# V_Sns_I2C_Isolators.net
KiCad netlist of a schematic drawn in Altium Designer
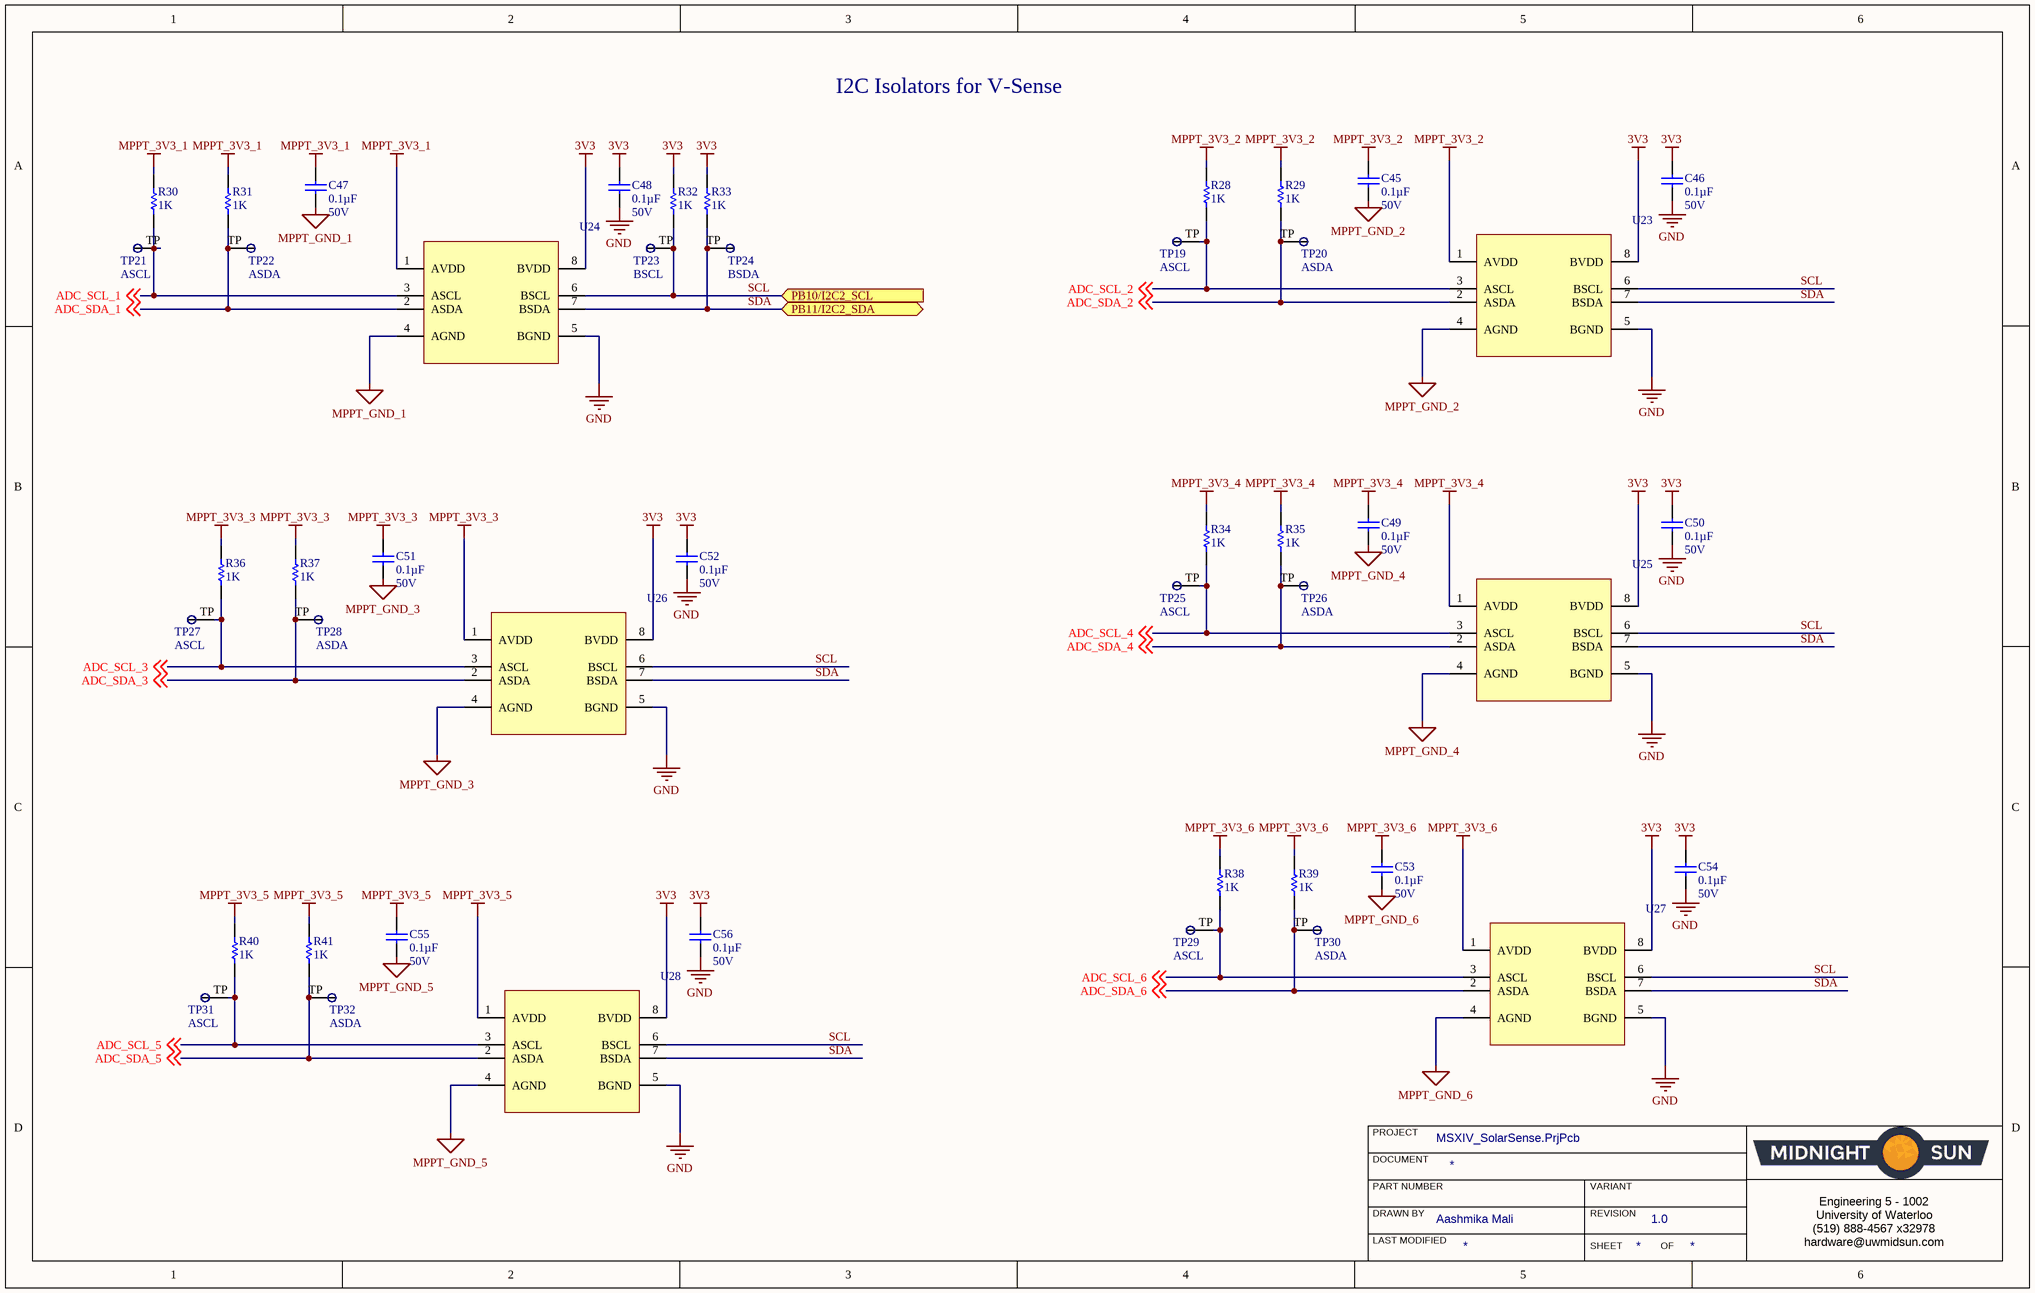
[diagram p0: V_Sns_I2C_Isolators.SchDoc]

(export (version "E")
  (design (tool "Eeschema 10.0.6"))
  (components
    (comp (ref "C45")
      (value "CAP CER 0.1UF 50V 10% X7R 0603")
      (footprint "CAP, 0603")
      (description "0.10µF ±10% 50V Ceramic Capacitor X7R 0603 (1608 Metric)")
      (fields
        (field (name "TOLERANCE") "±10%")
        (field (name "CAPACITANCE") "0.1µF")
        (field (name "VOLTAGE") "50V")
      )
      (libsource (lib "Schematic Diagrams") (part "CAP CER 0.1UF 50V 10% X7R 0603"))
    )
    (comp (ref "C46")
      (value "CAP CER 0.1UF 50V 10% X7R 0603")
      (footprint "CAP, 0603")
      (description "0.10µF ±10% 50V Ceramic Capacitor X7R 0603 (1608 Metric)")
      (fields
        (field (name "TOLERANCE") "±10%")
        (field (name "CAPACITANCE") "0.1µF")
        (field (name "VOLTAGE") "50V")
      )
      (libsource (lib "Schematic Diagrams") (part "CAP CER 0.1UF 50V 10% X7R 0603"))
    )
    (comp (ref "C47")
      (value "CAP CER 0.1UF 50V 10% X7R 0603")
      (footprint "CAP, 0603")
      (description "0.10µF ±10% 50V Ceramic Capacitor X7R 0603 (1608 Metric)")
      (fields
        (field (name "TOLERANCE") "±10%")
        (field (name "CAPACITANCE") "0.1µF")
        (field (name "VOLTAGE") "50V")
      )
      (libsource (lib "Schematic Diagrams") (part "CAP CER 0.1UF 50V 10% X7R 0603"))
    )
    (comp (ref "C48")
      (value "CAP CER 0.1UF 50V 10% X7R 0603")
      (footprint "CAP, 0603")
      (description "0.10µF ±10% 50V Ceramic Capacitor X7R 0603 (1608 Metric)")
      (fields
        (field (name "TOLERANCE") "±10%")
        (field (name "CAPACITANCE") "0.1µF")
        (field (name "VOLTAGE") "50V")
      )
      (libsource (lib "Schematic Diagrams") (part "CAP CER 0.1UF 50V 10% X7R 0603"))
    )
    (comp (ref "C49")
      (value "CAP CER 0.1UF 50V 10% X7R 0603")
      (footprint "CAP, 0603")
      (description "0.10µF ±10% 50V Ceramic Capacitor X7R 0603 (1608 Metric)")
      (fields
        (field (name "TOLERANCE") "±10%")
        (field (name "CAPACITANCE") "0.1µF")
        (field (name "VOLTAGE") "50V")
      )
      (libsource (lib "Schematic Diagrams") (part "CAP CER 0.1UF 50V 10% X7R 0603"))
    )
    (comp (ref "C50")
      (value "CAP CER 0.1UF 50V 10% X7R 0603")
      (footprint "CAP, 0603")
      (description "0.10µF ±10% 50V Ceramic Capacitor X7R 0603 (1608 Metric)")
      (fields
        (field (name "TOLERANCE") "±10%")
        (field (name "CAPACITANCE") "0.1µF")
        (field (name "VOLTAGE") "50V")
      )
      (libsource (lib "Schematic Diagrams") (part "CAP CER 0.1UF 50V 10% X7R 0603"))
    )
    (comp (ref "C51")
      (value "CAP CER 0.1UF 50V 10% X7R 0603")
      (footprint "CAP, 0603")
      (description "0.10µF ±10% 50V Ceramic Capacitor X7R 0603 (1608 Metric)")
      (fields
        (field (name "TOLERANCE") "±10%")
        (field (name "CAPACITANCE") "0.1µF")
        (field (name "VOLTAGE") "50V")
      )
      (libsource (lib "Schematic Diagrams") (part "CAP CER 0.1UF 50V 10% X7R 0603"))
    )
    (comp (ref "C52")
      (value "CAP CER 0.1UF 50V 10% X7R 0603")
      (footprint "CAP, 0603")
      (description "0.10µF ±10% 50V Ceramic Capacitor X7R 0603 (1608 Metric)")
      (fields
        (field (name "TOLERANCE") "±10%")
        (field (name "CAPACITANCE") "0.1µF")
        (field (name "VOLTAGE") "50V")
      )
      (libsource (lib "Schematic Diagrams") (part "CAP CER 0.1UF 50V 10% X7R 0603"))
    )
    (comp (ref "C53")
      (value "CAP CER 0.1UF 50V 10% X7R 0603")
      (footprint "CAP, 0603")
      (description "0.10µF ±10% 50V Ceramic Capacitor X7R 0603 (1608 Metric)")
      (fields
        (field (name "TOLERANCE") "±10%")
        (field (name "CAPACITANCE") "0.1µF")
        (field (name "VOLTAGE") "50V")
      )
      (libsource (lib "Schematic Diagrams") (part "CAP CER 0.1UF 50V 10% X7R 0603"))
    )
    (comp (ref "C54")
      (value "CAP CER 0.1UF 50V 10% X7R 0603")
      (footprint "CAP, 0603")
      (description "0.10µF ±10% 50V Ceramic Capacitor X7R 0603 (1608 Metric)")
      (fields
        (field (name "TOLERANCE") "±10%")
        (field (name "CAPACITANCE") "0.1µF")
        (field (name "VOLTAGE") "50V")
      )
      (libsource (lib "Schematic Diagrams") (part "CAP CER 0.1UF 50V 10% X7R 0603"))
    )
    (comp (ref "C55")
      (value "CAP CER 0.1UF 50V 10% X7R 0603")
      (footprint "CAP, 0603")
      (description "0.10µF ±10% 50V Ceramic Capacitor X7R 0603 (1608 Metric)")
      (fields
        (field (name "TOLERANCE") "±10%")
        (field (name "CAPACITANCE") "0.1µF")
        (field (name "VOLTAGE") "50V")
      )
      (libsource (lib "Schematic Diagrams") (part "CAP CER 0.1UF 50V 10% X7R 0603"))
    )
    (comp (ref "C56")
      (value "CAP CER 0.1UF 50V 10% X7R 0603")
      (footprint "CAP, 0603")
      (description "0.10µF ±10% 50V Ceramic Capacitor X7R 0603 (1608 Metric)")
      (fields
        (field (name "TOLERANCE") "±10%")
        (field (name "CAPACITANCE") "0.1µF")
        (field (name "VOLTAGE") "50V")
      )
      (libsource (lib "Schematic Diagrams") (part "CAP CER 0.1UF 50V 10% X7R 0603"))
    )
    (comp (ref "R28")
      (value "1K")
      (footprint "RES, 0603")
      (description "1k Ohm ±5% 0.1W, 1/10W Chip Resistor 0603 (1608 Metric)")
      (fields
        (field (name "MANUFACTURER") "Yageo")
        (field (name "MANUFACTURER PART NUMBER") "RC0603JR-071KL")
      )
      (libsource (lib "Schematic Diagrams") (part "RES 1K OHM 5% 1/10W 0603"))
    )
    (comp (ref "R29")
      (value "1K")
      (footprint "RES, 0603")
      (description "1k Ohm ±5% 0.1W, 1/10W Chip Resistor 0603 (1608 Metric)")
      (fields
        (field (name "MANUFACTURER") "Yageo")
        (field (name "MANUFACTURER PART NUMBER") "RC0603JR-071KL")
      )
      (libsource (lib "Schematic Diagrams") (part "RES 1K OHM 5% 1/10W 0603"))
    )
    (comp (ref "R30")
      (value "1K")
      (footprint "RES, 0603")
      (description "1k Ohm ±5% 0.1W, 1/10W Chip Resistor 0603 (1608 Metric)")
      (fields
        (field (name "MANUFACTURER") "Yageo")
        (field (name "MANUFACTURER PART NUMBER") "RC0603JR-071KL")
      )
      (libsource (lib "Schematic Diagrams") (part "RES 1K OHM 5% 1/10W 0603"))
    )
    (comp (ref "R31")
      (value "1K")
      (footprint "RES, 0603")
      (description "1k Ohm ±5% 0.1W, 1/10W Chip Resistor 0603 (1608 Metric)")
      (fields
        (field (name "MANUFACTURER") "Yageo")
        (field (name "MANUFACTURER PART NUMBER") "RC0603JR-071KL")
      )
      (libsource (lib "Schematic Diagrams") (part "RES 1K OHM 5% 1/10W 0603"))
    )
    (comp (ref "R32")
      (value "1K")
      (footprint "RES, 0603")
      (description "1k Ohm ±5% 0.1W, 1/10W Chip Resistor 0603 (1608 Metric)")
      (fields
        (field (name "MANUFACTURER") "Yageo")
        (field (name "MANUFACTURER PART NUMBER") "RC0603JR-071KL")
      )
      (libsource (lib "Schematic Diagrams") (part "RES 1K OHM 5% 1/10W 0603"))
    )
    (comp (ref "R33")
      (value "1K")
      (footprint "RES, 0603")
      (description "1k Ohm ±5% 0.1W, 1/10W Chip Resistor 0603 (1608 Metric)")
      (fields
        (field (name "MANUFACTURER") "Yageo")
        (field (name "MANUFACTURER PART NUMBER") "RC0603JR-071KL")
      )
      (libsource (lib "Schematic Diagrams") (part "RES 1K OHM 5% 1/10W 0603"))
    )
    (comp (ref "R34")
      (value "1K")
      (footprint "RES, 0603")
      (description "1k Ohm ±5% 0.1W, 1/10W Chip Resistor 0603 (1608 Metric)")
      (fields
        (field (name "MANUFACTURER") "Yageo")
        (field (name "MANUFACTURER PART NUMBER") "RC0603JR-071KL")
      )
      (libsource (lib "Schematic Diagrams") (part "RES 1K OHM 5% 1/10W 0603"))
    )
    (comp (ref "R35")
      (value "1K")
      (footprint "RES, 0603")
      (description "1k Ohm ±5% 0.1W, 1/10W Chip Resistor 0603 (1608 Metric)")
      (fields
        (field (name "MANUFACTURER") "Yageo")
        (field (name "MANUFACTURER PART NUMBER") "RC0603JR-071KL")
      )
      (libsource (lib "Schematic Diagrams") (part "RES 1K OHM 5% 1/10W 0603"))
    )
    (comp (ref "R36")
      (value "1K")
      (footprint "RES, 0603")
      (description "1k Ohm ±5% 0.1W, 1/10W Chip Resistor 0603 (1608 Metric)")
      (fields
        (field (name "MANUFACTURER") "Yageo")
        (field (name "MANUFACTURER PART NUMBER") "RC0603JR-071KL")
      )
      (libsource (lib "Schematic Diagrams") (part "RES 1K OHM 5% 1/10W 0603"))
    )
    (comp (ref "R37")
      (value "1K")
      (footprint "RES, 0603")
      (description "1k Ohm ±5% 0.1W, 1/10W Chip Resistor 0603 (1608 Metric)")
      (fields
        (field (name "MANUFACTURER") "Yageo")
        (field (name "MANUFACTURER PART NUMBER") "RC0603JR-071KL")
      )
      (libsource (lib "Schematic Diagrams") (part "RES 1K OHM 5% 1/10W 0603"))
    )
    (comp (ref "R38")
      (value "1K")
      (footprint "RES, 0603")
      (description "1k Ohm ±5% 0.1W, 1/10W Chip Resistor 0603 (1608 Metric)")
      (fields
        (field (name "MANUFACTURER") "Yageo")
        (field (name "MANUFACTURER PART NUMBER") "RC0603JR-071KL")
      )
      (libsource (lib "Schematic Diagrams") (part "RES 1K OHM 5% 1/10W 0603"))
    )
    (comp (ref "R39")
      (value "1K")
      (footprint "RES, 0603")
      (description "1k Ohm ±5% 0.1W, 1/10W Chip Resistor 0603 (1608 Metric)")
      (fields
        (field (name "MANUFACTURER") "Yageo")
        (field (name "MANUFACTURER PART NUMBER") "RC0603JR-071KL")
      )
      (libsource (lib "Schematic Diagrams") (part "RES 1K OHM 5% 1/10W 0603"))
    )
    (comp (ref "R40")
      (value "1K")
      (footprint "RES, 0603")
      (description "1k Ohm ±5% 0.1W, 1/10W Chip Resistor 0603 (1608 Metric)")
      (fields
        (field (name "MANUFACTURER") "Yageo")
        (field (name "MANUFACTURER PART NUMBER") "RC0603JR-071KL")
      )
      (libsource (lib "Schematic Diagrams") (part "RES 1K OHM 5% 1/10W 0603"))
    )
    (comp (ref "R41")
      (value "1K")
      (footprint "RES, 0603")
      (description "1k Ohm ±5% 0.1W, 1/10W Chip Resistor 0603 (1608 Metric)")
      (fields
        (field (name "MANUFACTURER") "Yageo")
        (field (name "MANUFACTURER PART NUMBER") "RC0603JR-071KL")
      )
      (libsource (lib "Schematic Diagrams") (part "RES 1K OHM 5% 1/10W 0603"))
    )
    (comp (ref "TP19")
      (value "ASCL")
      (footprint "Test Point")
      (libsource (lib "Schematic Diagrams") (part "Test Point"))
    )
    (comp (ref "TP20")
      (value "ASDA")
      (footprint "Test Point")
      (libsource (lib "Schematic Diagrams") (part "Test Point"))
    )
    (comp (ref "TP21")
      (value "ASCL")
      (footprint "Test Point")
      (libsource (lib "Schematic Diagrams") (part "Test Point"))
    )
    (comp (ref "TP22")
      (value "ASDA")
      (footprint "Test Point")
      (libsource (lib "Schematic Diagrams") (part "Test Point"))
    )
    (comp (ref "TP23")
      (value "BSCL")
      (footprint "Test Point")
      (libsource (lib "Schematic Diagrams") (part "Test Point"))
    )
    (comp (ref "TP24")
      (value "BSDA")
      (footprint "Test Point")
      (libsource (lib "Schematic Diagrams") (part "Test Point"))
    )
    (comp (ref "TP25")
      (value "ASCL")
      (footprint "Test Point")
      (libsource (lib "Schematic Diagrams") (part "Test Point"))
    )
    (comp (ref "TP26")
      (value "ASDA")
      (footprint "Test Point")
      (libsource (lib "Schematic Diagrams") (part "Test Point"))
    )
    (comp (ref "TP27")
      (value "ASCL")
      (footprint "Test Point")
      (libsource (lib "Schematic Diagrams") (part "Test Point"))
    )
    (comp (ref "TP28")
      (value "ASDA")
      (footprint "Test Point")
      (libsource (lib "Schematic Diagrams") (part "Test Point"))
    )
    (comp (ref "TP29")
      (value "ASCL")
      (footprint "Test Point")
      (libsource (lib "Schematic Diagrams") (part "Test Point"))
    )
    (comp (ref "TP30")
      (value "ASDA")
      (footprint "Test Point")
      (libsource (lib "Schematic Diagrams") (part "Test Point"))
    )
    (comp (ref "TP31")
      (value "ASCL")
      (footprint "Test Point")
      (libsource (lib "Schematic Diagrams") (part "Test Point"))
    )
    (comp (ref "TP32")
      (value "ASDA")
      (footprint "Test Point")
      (libsource (lib "Schematic Diagrams") (part "Test Point"))
    )
    (comp (ref "U23")
      (value "IC DGTL ISO 2.5KV 2CH I2C 8SOIC ISO1540DR")
      (footprint "SOIC-8 ISO1540DR")
      (description "I²C Digital Isolator 2500Vrms 2 Channel 1Mbps 25kV/µs CMTI 8-SOIC (0.154\", 3.90mm Width)")
      (fields
        (field (name "MANUFACTURER") "Texas Instruments")
        (field (name "MANUFACTURER PART NUMBER") "ISO1540DR")
      )
      (libsource (lib "Schematic Diagrams") (part "IC DGTL ISO 2.5KV 2CH I2C 8SOIC ISO1540DR"))
    )
    (comp (ref "U24")
      (value "IC DGTL ISO 2.5KV 2CH I2C 8SOIC ISO1540DR")
      (footprint "SOIC-8 ISO1540DR")
      (description "I²C Digital Isolator 2500Vrms 2 Channel 1Mbps 25kV/µs CMTI 8-SOIC (0.154\", 3.90mm Width)")
      (fields
        (field (name "MANUFACTURER") "Texas Instruments")
        (field (name "MANUFACTURER PART NUMBER") "ISO1540DR")
      )
      (libsource (lib "Schematic Diagrams") (part "IC DGTL ISO 2.5KV 2CH I2C 8SOIC ISO1540DR"))
    )
    (comp (ref "U25")
      (value "IC DGTL ISO 2.5KV 2CH I2C 8SOIC ISO1540DR")
      (footprint "SOIC-8 ISO1540DR")
      (description "I²C Digital Isolator 2500Vrms 2 Channel 1Mbps 25kV/µs CMTI 8-SOIC (0.154\", 3.90mm Width)")
      (fields
        (field (name "MANUFACTURER") "Texas Instruments")
        (field (name "MANUFACTURER PART NUMBER") "ISO1540DR")
      )
      (libsource (lib "Schematic Diagrams") (part "IC DGTL ISO 2.5KV 2CH I2C 8SOIC ISO1540DR"))
    )
    (comp (ref "U26")
      (value "IC DGTL ISO 2.5KV 2CH I2C 8SOIC ISO1540DR")
      (footprint "SOIC-8 ISO1540DR")
      (description "I²C Digital Isolator 2500Vrms 2 Channel 1Mbps 25kV/µs CMTI 8-SOIC (0.154\", 3.90mm Width)")
      (fields
        (field (name "MANUFACTURER") "Texas Instruments")
        (field (name "MANUFACTURER PART NUMBER") "ISO1540DR")
      )
      (libsource (lib "Schematic Diagrams") (part "IC DGTL ISO 2.5KV 2CH I2C 8SOIC ISO1540DR"))
    )
    (comp (ref "U27")
      (value "IC DGTL ISO 2.5KV 2CH I2C 8SOIC ISO1540DR")
      (footprint "SOIC-8 ISO1540DR")
      (description "I²C Digital Isolator 2500Vrms 2 Channel 1Mbps 25kV/µs CMTI 8-SOIC (0.154\", 3.90mm Width)")
      (fields
        (field (name "MANUFACTURER") "Texas Instruments")
        (field (name "MANUFACTURER PART NUMBER") "ISO1540DR")
      )
      (libsource (lib "Schematic Diagrams") (part "IC DGTL ISO 2.5KV 2CH I2C 8SOIC ISO1540DR"))
    )
    (comp (ref "U28")
      (value "IC DGTL ISO 2.5KV 2CH I2C 8SOIC ISO1540DR")
      (footprint "SOIC-8 ISO1540DR")
      (description "I²C Digital Isolator 2500Vrms 2 Channel 1Mbps 25kV/µs CMTI 8-SOIC (0.154\", 3.90mm Width)")
      (fields
        (field (name "MANUFACTURER") "Texas Instruments")
        (field (name "MANUFACTURER PART NUMBER") "ISO1540DR")
      )
      (libsource (lib "Schematic Diagrams") (part "IC DGTL ISO 2.5KV 2CH I2C 8SOIC ISO1540DR"))
    )
  )
  (nets
    (net (code "1") (name "/SCL") (class "Default")
      (node (ref "R32") (pin "2") (pinfunction "2_2") (pintype "passive"))
      (node (ref "TP23") (pin "TP") (pinfunction "1_TP") (pintype "passive"))
      (node (ref "U23") (pin "6") (pinfunction "BSCL_6") (pintype "passive"))
      (node (ref "U24") (pin "6") (pinfunction "BSCL_6") (pintype "passive"))
      (node (ref "U25") (pin "6") (pinfunction "BSCL_6") (pintype "passive"))
      (node (ref "U26") (pin "6") (pinfunction "BSCL_6") (pintype "passive"))
      (node (ref "U27") (pin "6") (pinfunction "BSCL_6") (pintype "passive"))
      (node (ref "U28") (pin "6") (pinfunction "BSCL_6") (pintype "passive"))
    )
    (net (code "2") (name "/SDA") (class "Default")
      (node (ref "R33") (pin "2") (pinfunction "2_2") (pintype "passive"))
      (node (ref "TP24") (pin "TP") (pinfunction "1_TP") (pintype "passive"))
      (node (ref "U23") (pin "7") (pinfunction "BSDA_7") (pintype "passive"))
      (node (ref "U24") (pin "7") (pinfunction "BSDA_7") (pintype "passive"))
      (node (ref "U25") (pin "7") (pinfunction "BSDA_7") (pintype "passive"))
      (node (ref "U26") (pin "7") (pinfunction "BSDA_7") (pintype "passive"))
      (node (ref "U27") (pin "7") (pinfunction "BSDA_7") (pintype "passive"))
      (node (ref "U28") (pin "7") (pinfunction "BSDA_7") (pintype "passive"))
    )
    (net (code "3") (name "3V3") (class "Default")
      (node (ref "C46") (pin "1") (pinfunction "1_1") (pintype "passive"))
      (node (ref "C48") (pin "1") (pinfunction "1_1") (pintype "passive"))
      (node (ref "C50") (pin "1") (pinfunction "1_1") (pintype "passive"))
      (node (ref "C52") (pin "1") (pinfunction "1_1") (pintype "passive"))
      (node (ref "C54") (pin "1") (pinfunction "1_1") (pintype "passive"))
      (node (ref "C56") (pin "1") (pinfunction "1_1") (pintype "passive"))
      (node (ref "R32") (pin "1") (pinfunction "1_1") (pintype "passive"))
      (node (ref "R33") (pin "1") (pinfunction "1_1") (pintype "passive"))
      (node (ref "U23") (pin "8") (pinfunction "BVDD_8") (pintype "passive"))
      (node (ref "U24") (pin "8") (pinfunction "BVDD_8") (pintype "passive"))
      (node (ref "U25") (pin "8") (pinfunction "BVDD_8") (pintype "passive"))
      (node (ref "U26") (pin "8") (pinfunction "BVDD_8") (pintype "passive"))
      (node (ref "U27") (pin "8") (pinfunction "BVDD_8") (pintype "passive"))
      (node (ref "U28") (pin "8") (pinfunction "BVDD_8") (pintype "passive"))
    )
    (net (code "4") (name "ADC_SCL_1") (class "Default")
      (node (ref "R30") (pin "2") (pinfunction "2_2") (pintype "passive"))
      (node (ref "TP21") (pin "TP") (pinfunction "1_TP") (pintype "passive"))
      (node (ref "U24") (pin "3") (pinfunction "ASCL_3") (pintype "open_collector"))
    )
    (net (code "5") (name "ADC_SCL_2") (class "Default")
      (node (ref "R28") (pin "2") (pinfunction "2_2") (pintype "passive"))
      (node (ref "TP19") (pin "TP") (pinfunction "1_TP") (pintype "passive"))
      (node (ref "U23") (pin "3") (pinfunction "ASCL_3") (pintype "open_collector"))
    )
    (net (code "6") (name "ADC_SCL_3") (class "Default")
      (node (ref "R36") (pin "2") (pinfunction "2_2") (pintype "passive"))
      (node (ref "TP27") (pin "TP") (pinfunction "1_TP") (pintype "passive"))
      (node (ref "U26") (pin "3") (pinfunction "ASCL_3") (pintype "open_collector"))
    )
    (net (code "7") (name "ADC_SCL_4") (class "Default")
      (node (ref "R34") (pin "2") (pinfunction "2_2") (pintype "passive"))
      (node (ref "TP25") (pin "TP") (pinfunction "1_TP") (pintype "passive"))
      (node (ref "U25") (pin "3") (pinfunction "ASCL_3") (pintype "open_collector"))
    )
    (net (code "8") (name "ADC_SCL_5") (class "Default")
      (node (ref "R40") (pin "2") (pinfunction "2_2") (pintype "passive"))
      (node (ref "TP31") (pin "TP") (pinfunction "1_TP") (pintype "passive"))
      (node (ref "U28") (pin "3") (pinfunction "ASCL_3") (pintype "open_collector"))
    )
    (net (code "9") (name "ADC_SCL_6") (class "Default")
      (node (ref "R38") (pin "2") (pinfunction "2_2") (pintype "passive"))
      (node (ref "TP29") (pin "TP") (pinfunction "1_TP") (pintype "passive"))
      (node (ref "U27") (pin "3") (pinfunction "ASCL_3") (pintype "open_collector"))
    )
    (net (code "10") (name "ADC_SDA_1") (class "Default")
      (node (ref "R31") (pin "2") (pinfunction "2_2") (pintype "passive"))
      (node (ref "TP22") (pin "TP") (pinfunction "1_TP") (pintype "passive"))
      (node (ref "U24") (pin "2") (pinfunction "ASDA_2") (pintype "open_collector"))
    )
    (net (code "11") (name "ADC_SDA_2") (class "Default")
      (node (ref "R29") (pin "2") (pinfunction "2_2") (pintype "passive"))
      (node (ref "TP20") (pin "TP") (pinfunction "1_TP") (pintype "passive"))
      (node (ref "U23") (pin "2") (pinfunction "ASDA_2") (pintype "open_collector"))
    )
    (net (code "12") (name "ADC_SDA_3") (class "Default")
      (node (ref "R37") (pin "2") (pinfunction "2_2") (pintype "passive"))
      (node (ref "TP28") (pin "TP") (pinfunction "1_TP") (pintype "passive"))
      (node (ref "U26") (pin "2") (pinfunction "ASDA_2") (pintype "open_collector"))
    )
    (net (code "13") (name "ADC_SDA_4") (class "Default")
      (node (ref "R35") (pin "2") (pinfunction "2_2") (pintype "passive"))
      (node (ref "TP26") (pin "TP") (pinfunction "1_TP") (pintype "passive"))
      (node (ref "U25") (pin "2") (pinfunction "ASDA_2") (pintype "open_collector"))
    )
    (net (code "14") (name "ADC_SDA_5") (class "Default")
      (node (ref "R41") (pin "2") (pinfunction "2_2") (pintype "passive"))
      (node (ref "TP32") (pin "TP") (pinfunction "1_TP") (pintype "passive"))
      (node (ref "U28") (pin "2") (pinfunction "ASDA_2") (pintype "open_collector"))
    )
    (net (code "15") (name "ADC_SDA_6") (class "Default")
      (node (ref "R39") (pin "2") (pinfunction "2_2") (pintype "passive"))
      (node (ref "TP30") (pin "TP") (pinfunction "1_TP") (pintype "passive"))
      (node (ref "U27") (pin "2") (pinfunction "ASDA_2") (pintype "open_collector"))
    )
    (net (code "16") (name "GND") (class "Default")
      (node (ref "C46") (pin "2") (pinfunction "2_2") (pintype "passive"))
      (node (ref "C48") (pin "2") (pinfunction "2_2") (pintype "passive"))
      (node (ref "C50") (pin "2") (pinfunction "2_2") (pintype "passive"))
      (node (ref "C52") (pin "2") (pinfunction "2_2") (pintype "passive"))
      (node (ref "C54") (pin "2") (pinfunction "2_2") (pintype "passive"))
      (node (ref "C56") (pin "2") (pinfunction "2_2") (pintype "passive"))
      (node (ref "U23") (pin "5") (pinfunction "BGND_5") (pintype "passive"))
      (node (ref "U24") (pin "5") (pinfunction "BGND_5") (pintype "passive"))
      (node (ref "U25") (pin "5") (pinfunction "BGND_5") (pintype "passive"))
      (node (ref "U26") (pin "5") (pinfunction "BGND_5") (pintype "passive"))
      (node (ref "U27") (pin "5") (pinfunction "BGND_5") (pintype "passive"))
      (node (ref "U28") (pin "5") (pinfunction "BGND_5") (pintype "passive"))
    )
    (net (code "17") (name "MPPT_3V3_1") (class "Default")
      (node (ref "C47") (pin "1") (pinfunction "1_1") (pintype "passive"))
      (node (ref "R30") (pin "1") (pinfunction "1_1") (pintype "passive"))
      (node (ref "R31") (pin "1") (pinfunction "1_1") (pintype "passive"))
      (node (ref "U24") (pin "1") (pinfunction "AVDD_1") (pintype "passive"))
    )
    (net (code "18") (name "MPPT_3V3_2") (class "Default")
      (node (ref "C45") (pin "1") (pinfunction "1_1") (pintype "passive"))
      (node (ref "R28") (pin "1") (pinfunction "1_1") (pintype "passive"))
      (node (ref "R29") (pin "1") (pinfunction "1_1") (pintype "passive"))
      (node (ref "U23") (pin "1") (pinfunction "AVDD_1") (pintype "passive"))
    )
    (net (code "19") (name "MPPT_3V3_3") (class "Default")
      (node (ref "C51") (pin "1") (pinfunction "1_1") (pintype "passive"))
      (node (ref "R36") (pin "1") (pinfunction "1_1") (pintype "passive"))
      (node (ref "R37") (pin "1") (pinfunction "1_1") (pintype "passive"))
      (node (ref "U26") (pin "1") (pinfunction "AVDD_1") (pintype "passive"))
    )
    (net (code "20") (name "MPPT_3V3_4") (class "Default")
      (node (ref "C49") (pin "1") (pinfunction "1_1") (pintype "passive"))
      (node (ref "R34") (pin "1") (pinfunction "1_1") (pintype "passive"))
      (node (ref "R35") (pin "1") (pinfunction "1_1") (pintype "passive"))
      (node (ref "U25") (pin "1") (pinfunction "AVDD_1") (pintype "passive"))
    )
    (net (code "21") (name "MPPT_3V3_5") (class "Default")
      (node (ref "C55") (pin "1") (pinfunction "1_1") (pintype "passive"))
      (node (ref "R40") (pin "1") (pinfunction "1_1") (pintype "passive"))
      (node (ref "R41") (pin "1") (pinfunction "1_1") (pintype "passive"))
      (node (ref "U28") (pin "1") (pinfunction "AVDD_1") (pintype "passive"))
    )
    (net (code "22") (name "MPPT_3V3_6") (class "Default")
      (node (ref "C53") (pin "1") (pinfunction "1_1") (pintype "passive"))
      (node (ref "R38") (pin "1") (pinfunction "1_1") (pintype "passive"))
      (node (ref "R39") (pin "1") (pinfunction "1_1") (pintype "passive"))
      (node (ref "U27") (pin "1") (pinfunction "AVDD_1") (pintype "passive"))
    )
    (net (code "23") (name "MPPT_GND_1") (class "Default")
      (node (ref "C47") (pin "2") (pinfunction "2_2") (pintype "passive"))
      (node (ref "U24") (pin "4") (pinfunction "AGND_4") (pintype "passive"))
    )
    (net (code "24") (name "MPPT_GND_2") (class "Default")
      (node (ref "C45") (pin "2") (pinfunction "2_2") (pintype "passive"))
      (node (ref "U23") (pin "4") (pinfunction "AGND_4") (pintype "passive"))
    )
    (net (code "25") (name "MPPT_GND_3") (class "Default")
      (node (ref "C51") (pin "2") (pinfunction "2_2") (pintype "passive"))
      (node (ref "U26") (pin "4") (pinfunction "AGND_4") (pintype "passive"))
    )
    (net (code "26") (name "MPPT_GND_4") (class "Default")
      (node (ref "C49") (pin "2") (pinfunction "2_2") (pintype "passive"))
      (node (ref "U25") (pin "4") (pinfunction "AGND_4") (pintype "passive"))
    )
    (net (code "27") (name "MPPT_GND_5") (class "Default")
      (node (ref "C55") (pin "2") (pinfunction "2_2") (pintype "passive"))
      (node (ref "U28") (pin "4") (pinfunction "AGND_4") (pintype "passive"))
    )
    (net (code "28") (name "MPPT_GND_6") (class "Default")
      (node (ref "C53") (pin "2") (pinfunction "2_2") (pintype "passive"))
      (node (ref "U27") (pin "4") (pinfunction "AGND_4") (pintype "passive"))
    )
  )
)
